# Memory.net
KiCad netlist of a schematic drawn in Altium Designer
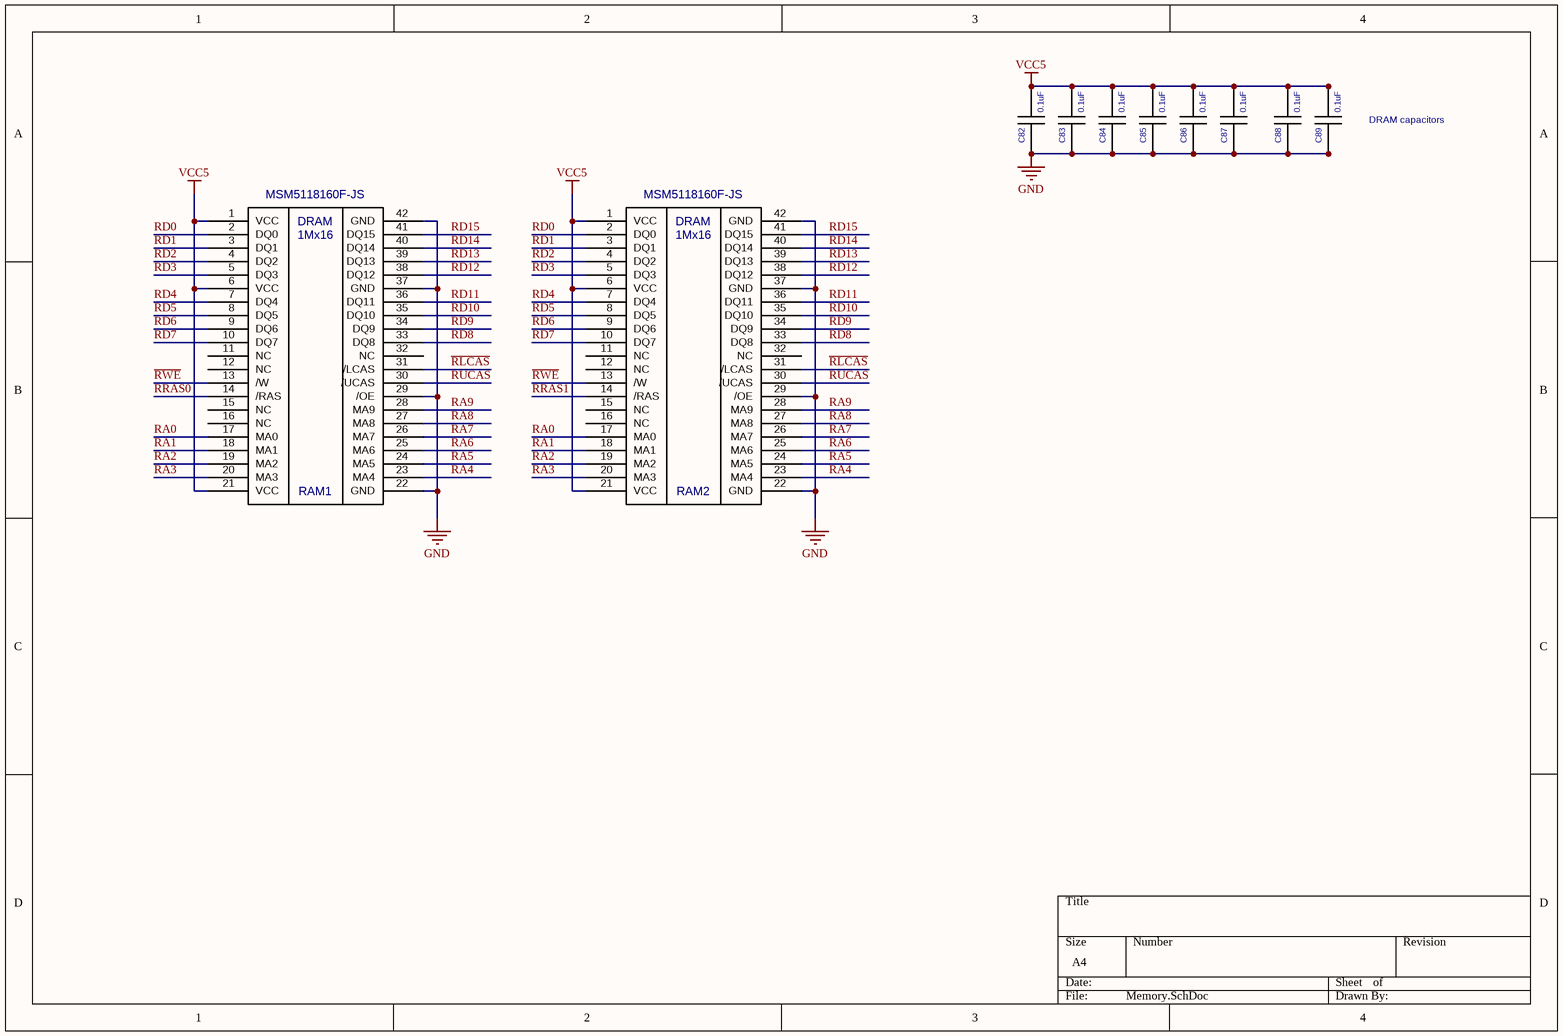
[diagram p0: Memory.SchDoc]

(export (version "E")
  (design (tool "Eeschema 10.0.6"))
  (components
    (comp (ref "C82")
      (value "0.1uF")
      (footprint "C-CHIP")
      (description "CAPCHIP")
      (libsource (lib "*") (part "CAPCHIP"))
    )
    (comp (ref "C83")
      (value "0.1uF")
      (footprint "C-CHIP")
      (description "CAPCHIP")
      (libsource (lib "*") (part "CAPCHIP"))
    )
    (comp (ref "C84")
      (value "0.1uF")
      (footprint "C-CHIP")
      (description "CAPCHIP")
      (libsource (lib "*") (part "CAPCHIP"))
    )
    (comp (ref "C85")
      (value "0.1uF")
      (footprint "C-CHIP")
      (description "CAPCHIP")
      (libsource (lib "*") (part "CAPCHIP"))
    )
    (comp (ref "C86")
      (value "0.1uF")
      (footprint "C-CHIP")
      (description "CAPCHIP")
      (libsource (lib "*") (part "CAPCHIP"))
    )
    (comp (ref "C87")
      (value "0.1uF")
      (footprint "C-CHIP")
      (description "CAPCHIP")
      (libsource (lib "*") (part "CAPCHIP"))
    )
    (comp (ref "C88")
      (value "0.1uF")
      (footprint "C-CHIP")
      (description "CAPCHIP")
      (libsource (lib "*") (part "CAPCHIP"))
    )
    (comp (ref "C89")
      (value "0.1uF")
      (footprint "C-CHIP")
      (description "CAPCHIP")
      (libsource (lib "*") (part "CAPCHIP"))
    )
    (comp (ref "RAM1")
      (value "MSM5118160F-JS")
      (footprint "SOJ42")
      (libsource (lib "*") (part "MSM5118160F-JS"))
    )
    (comp (ref "RAM2")
      (value "MSM5118160F-JS")
      (footprint "SOJ42")
      (libsource (lib "*") (part "MSM5118160F-JS"))
    )
  )
  (nets
    (net (code "1") (name "/RA0") (class "Default")
      (node (ref "RAM1") (pin "17") (pinfunction "MA0_17") (pintype "passive"))
      (node (ref "RAM2") (pin "17") (pinfunction "MA0_17") (pintype "passive"))
    )
    (net (code "2") (name "/RA1") (class "Default")
      (node (ref "RAM1") (pin "18") (pinfunction "MA1_18") (pintype "passive"))
      (node (ref "RAM2") (pin "18") (pinfunction "MA1_18") (pintype "passive"))
    )
    (net (code "3") (name "/RA2") (class "Default")
      (node (ref "RAM1") (pin "19") (pinfunction "MA2_19") (pintype "passive"))
      (node (ref "RAM2") (pin "19") (pinfunction "MA2_19") (pintype "passive"))
    )
    (net (code "4") (name "/RA3") (class "Default")
      (node (ref "RAM1") (pin "20") (pinfunction "MA3_20") (pintype "passive"))
      (node (ref "RAM2") (pin "20") (pinfunction "MA3_20") (pintype "passive"))
    )
    (net (code "5") (name "/RA4") (class "Default")
      (node (ref "RAM1") (pin "23") (pinfunction "MA4_23") (pintype "passive"))
      (node (ref "RAM2") (pin "23") (pinfunction "MA4_23") (pintype "passive"))
    )
    (net (code "6") (name "/RA5") (class "Default")
      (node (ref "RAM1") (pin "24") (pinfunction "MA5_24") (pintype "passive"))
      (node (ref "RAM2") (pin "24") (pinfunction "MA5_24") (pintype "passive"))
    )
    (net (code "7") (name "/RA6") (class "Default")
      (node (ref "RAM1") (pin "25") (pinfunction "MA6_25") (pintype "passive"))
      (node (ref "RAM2") (pin "25") (pinfunction "MA6_25") (pintype "passive"))
    )
    (net (code "8") (name "/RA7") (class "Default")
      (node (ref "RAM1") (pin "26") (pinfunction "MA7_26") (pintype "passive"))
      (node (ref "RAM2") (pin "26") (pinfunction "MA7_26") (pintype "passive"))
    )
    (net (code "9") (name "/RA8") (class "Default")
      (node (ref "RAM1") (pin "27") (pinfunction "MA8_27") (pintype "passive"))
      (node (ref "RAM2") (pin "27") (pinfunction "MA8_27") (pintype "passive"))
    )
    (net (code "10") (name "/RA9") (class "Default")
      (node (ref "RAM1") (pin "28") (pinfunction "MA9_28") (pintype "passive"))
      (node (ref "RAM2") (pin "28") (pinfunction "MA9_28") (pintype "passive"))
    )
    (net (code "11") (name "/RD0") (class "Default")
      (node (ref "RAM1") (pin "2") (pinfunction "DQ0_2") (pintype "passive"))
      (node (ref "RAM2") (pin "2") (pinfunction "DQ0_2") (pintype "passive"))
    )
    (net (code "12") (name "/RD1") (class "Default")
      (node (ref "RAM1") (pin "3") (pinfunction "DQ1_3") (pintype "passive"))
      (node (ref "RAM2") (pin "3") (pinfunction "DQ1_3") (pintype "passive"))
    )
    (net (code "13") (name "/RD2") (class "Default")
      (node (ref "RAM1") (pin "4") (pinfunction "DQ2_4") (pintype "passive"))
      (node (ref "RAM2") (pin "4") (pinfunction "DQ2_4") (pintype "passive"))
    )
    (net (code "14") (name "/RD3") (class "Default")
      (node (ref "RAM1") (pin "5") (pinfunction "DQ3_5") (pintype "passive"))
      (node (ref "RAM2") (pin "5") (pinfunction "DQ3_5") (pintype "passive"))
    )
    (net (code "15") (name "/RD4") (class "Default")
      (node (ref "RAM1") (pin "7") (pinfunction "DQ4_7") (pintype "passive"))
      (node (ref "RAM2") (pin "7") (pinfunction "DQ4_7") (pintype "passive"))
    )
    (net (code "16") (name "/RD5") (class "Default")
      (node (ref "RAM1") (pin "8") (pinfunction "DQ5_8") (pintype "passive"))
      (node (ref "RAM2") (pin "8") (pinfunction "DQ5_8") (pintype "passive"))
    )
    (net (code "17") (name "/RD6") (class "Default")
      (node (ref "RAM1") (pin "9") (pinfunction "DQ6_9") (pintype "passive"))
      (node (ref "RAM2") (pin "9") (pinfunction "DQ6_9") (pintype "passive"))
    )
    (net (code "18") (name "/RD7") (class "Default")
      (node (ref "RAM1") (pin "10") (pinfunction "DQ7_10") (pintype "passive"))
      (node (ref "RAM2") (pin "10") (pinfunction "DQ7_10") (pintype "passive"))
    )
    (net (code "19") (name "/RD8") (class "Default")
      (node (ref "RAM1") (pin "33") (pinfunction "DQ8_33") (pintype "passive"))
      (node (ref "RAM2") (pin "33") (pinfunction "DQ8_33") (pintype "passive"))
    )
    (net (code "20") (name "/RD9") (class "Default")
      (node (ref "RAM1") (pin "34") (pinfunction "DQ9_34") (pintype "passive"))
      (node (ref "RAM2") (pin "34") (pinfunction "DQ9_34") (pintype "passive"))
    )
    (net (code "21") (name "/RD10") (class "Default")
      (node (ref "RAM1") (pin "35") (pinfunction "DQ10_35") (pintype "passive"))
      (node (ref "RAM2") (pin "35") (pinfunction "DQ10_35") (pintype "passive"))
    )
    (net (code "22") (name "/RD11") (class "Default")
      (node (ref "RAM1") (pin "36") (pinfunction "DQ11_36") (pintype "passive"))
      (node (ref "RAM2") (pin "36") (pinfunction "DQ11_36") (pintype "passive"))
    )
    (net (code "23") (name "/RD12") (class "Default")
      (node (ref "RAM1") (pin "38") (pinfunction "DQ12_38") (pintype "passive"))
      (node (ref "RAM2") (pin "38") (pinfunction "DQ12_38") (pintype "passive"))
    )
    (net (code "24") (name "/RD13") (class "Default")
      (node (ref "RAM1") (pin "39") (pinfunction "DQ13_39") (pintype "passive"))
      (node (ref "RAM2") (pin "39") (pinfunction "DQ13_39") (pintype "passive"))
    )
    (net (code "25") (name "/RD14") (class "Default")
      (node (ref "RAM1") (pin "40") (pinfunction "DQ14_40") (pintype "passive"))
      (node (ref "RAM2") (pin "40") (pinfunction "DQ14_40") (pintype "passive"))
    )
    (net (code "26") (name "/RD15") (class "Default")
      (node (ref "RAM1") (pin "41") (pinfunction "DQ15_41") (pintype "passive"))
      (node (ref "RAM2") (pin "41") (pinfunction "DQ15_41") (pintype "passive"))
    )
    (net (code "27") (name "/~{RLCAS}") (class "Default")
      (node (ref "RAM1") (pin "31") (pinfunction "/LCAS_31") (pintype "passive"))
      (node (ref "RAM2") (pin "31") (pinfunction "/LCAS_31") (pintype "passive"))
    )
    (net (code "28") (name "/~{RRAS0}") (class "Default")
      (node (ref "RAM1") (pin "14") (pinfunction "/RAS_14") (pintype "passive"))
    )
    (net (code "29") (name "/~{RRAS1}") (class "Default")
      (node (ref "RAM2") (pin "14") (pinfunction "/RAS_14") (pintype "passive"))
    )
    (net (code "30") (name "/~{RUCAS}") (class "Default")
      (node (ref "RAM1") (pin "30") (pinfunction "/UCAS_30") (pintype "passive"))
      (node (ref "RAM2") (pin "30") (pinfunction "/UCAS_30") (pintype "passive"))
    )
    (net (code "31") (name "/~{RWE}") (class "Default")
      (node (ref "RAM1") (pin "13") (pinfunction "/W_13") (pintype "passive"))
      (node (ref "RAM2") (pin "13") (pinfunction "/W_13") (pintype "passive"))
    )
    (net (code "32") (name "GND") (class "Default")
      (node (ref "C82") (pin "1") (pinfunction "1_1") (pintype "passive"))
      (node (ref "C83") (pin "1") (pinfunction "1_1") (pintype "passive"))
      (node (ref "C84") (pin "1") (pinfunction "1_1") (pintype "passive"))
      (node (ref "C85") (pin "1") (pinfunction "1_1") (pintype "passive"))
      (node (ref "C86") (pin "1") (pinfunction "1_1") (pintype "passive"))
      (node (ref "C87") (pin "1") (pinfunction "1_1") (pintype "passive"))
      (node (ref "C88") (pin "1") (pinfunction "1_1") (pintype "passive"))
      (node (ref "C89") (pin "1") (pinfunction "1_1") (pintype "passive"))
      (node (ref "RAM1") (pin "22") (pinfunction "GND_22") (pintype "passive"))
      (node (ref "RAM1") (pin "29") (pinfunction "/OE_29") (pintype "passive"))
      (node (ref "RAM1") (pin "37") (pinfunction "GND_37") (pintype "passive"))
      (node (ref "RAM1") (pin "42") (pinfunction "GND_42") (pintype "passive"))
      (node (ref "RAM2") (pin "22") (pinfunction "GND_22") (pintype "passive"))
      (node (ref "RAM2") (pin "29") (pinfunction "/OE_29") (pintype "passive"))
      (node (ref "RAM2") (pin "37") (pinfunction "GND_37") (pintype "passive"))
      (node (ref "RAM2") (pin "42") (pinfunction "GND_42") (pintype "passive"))
    )
    (net (code "33") (name "VCC5") (class "Default")
      (node (ref "C82") (pin "2") (pinfunction "2_2") (pintype "passive"))
      (node (ref "C83") (pin "2") (pinfunction "2_2") (pintype "passive"))
      (node (ref "C84") (pin "2") (pinfunction "2_2") (pintype "passive"))
      (node (ref "C85") (pin "2") (pinfunction "2_2") (pintype "passive"))
      (node (ref "C86") (pin "2") (pinfunction "2_2") (pintype "passive"))
      (node (ref "C87") (pin "2") (pinfunction "2_2") (pintype "passive"))
      (node (ref "C88") (pin "2") (pinfunction "2_2") (pintype "passive"))
      (node (ref "C89") (pin "2") (pinfunction "2_2") (pintype "passive"))
      (node (ref "RAM1") (pin "1") (pinfunction "VCC_1") (pintype "passive"))
      (node (ref "RAM1") (pin "21") (pinfunction "VCC_21") (pintype "passive"))
      (node (ref "RAM1") (pin "6") (pinfunction "VCC_6") (pintype "passive"))
      (node (ref "RAM2") (pin "1") (pinfunction "VCC_1") (pintype "passive"))
      (node (ref "RAM2") (pin "21") (pinfunction "VCC_21") (pintype "passive"))
      (node (ref "RAM2") (pin "6") (pinfunction "VCC_6") (pintype "passive"))
    )
    (net (code "34") (name "unconnected-(RAM1-NC-Pad11)") (class "Default")
      (node (ref "RAM1") (pin "11") (pinfunction "NC_11") (pintype "passive"))
    )
    (net (code "35") (name "unconnected-(RAM1-NC-Pad12)") (class "Default")
      (node (ref "RAM1") (pin "12") (pinfunction "NC_12") (pintype "passive"))
    )
    (net (code "36") (name "unconnected-(RAM1-NC-Pad15)") (class "Default")
      (node (ref "RAM1") (pin "15") (pinfunction "NC_15") (pintype "passive"))
    )
    (net (code "37") (name "unconnected-(RAM1-NC-Pad16)") (class "Default")
      (node (ref "RAM1") (pin "16") (pinfunction "NC_16") (pintype "passive"))
    )
    (net (code "38") (name "unconnected-(RAM1-NC-Pad32)") (class "Default")
      (node (ref "RAM1") (pin "32") (pinfunction "NC_32") (pintype "passive"))
    )
    (net (code "39") (name "unconnected-(RAM2-NC-Pad11)") (class "Default")
      (node (ref "RAM2") (pin "11") (pinfunction "NC_11") (pintype "passive"))
    )
    (net (code "40") (name "unconnected-(RAM2-NC-Pad12)") (class "Default")
      (node (ref "RAM2") (pin "12") (pinfunction "NC_12") (pintype "passive"))
    )
    (net (code "41") (name "unconnected-(RAM2-NC-Pad15)") (class "Default")
      (node (ref "RAM2") (pin "15") (pinfunction "NC_15") (pintype "passive"))
    )
    (net (code "42") (name "unconnected-(RAM2-NC-Pad16)") (class "Default")
      (node (ref "RAM2") (pin "16") (pinfunction "NC_16") (pintype "passive"))
    )
    (net (code "43") (name "unconnected-(RAM2-NC-Pad32)") (class "Default")
      (node (ref "RAM2") (pin "32") (pinfunction "NC_32") (pintype "passive"))
    )
  )
)
